# Chime_PCB_v2_511.net
KiCad netlist of a schematic drawn in EAGLE
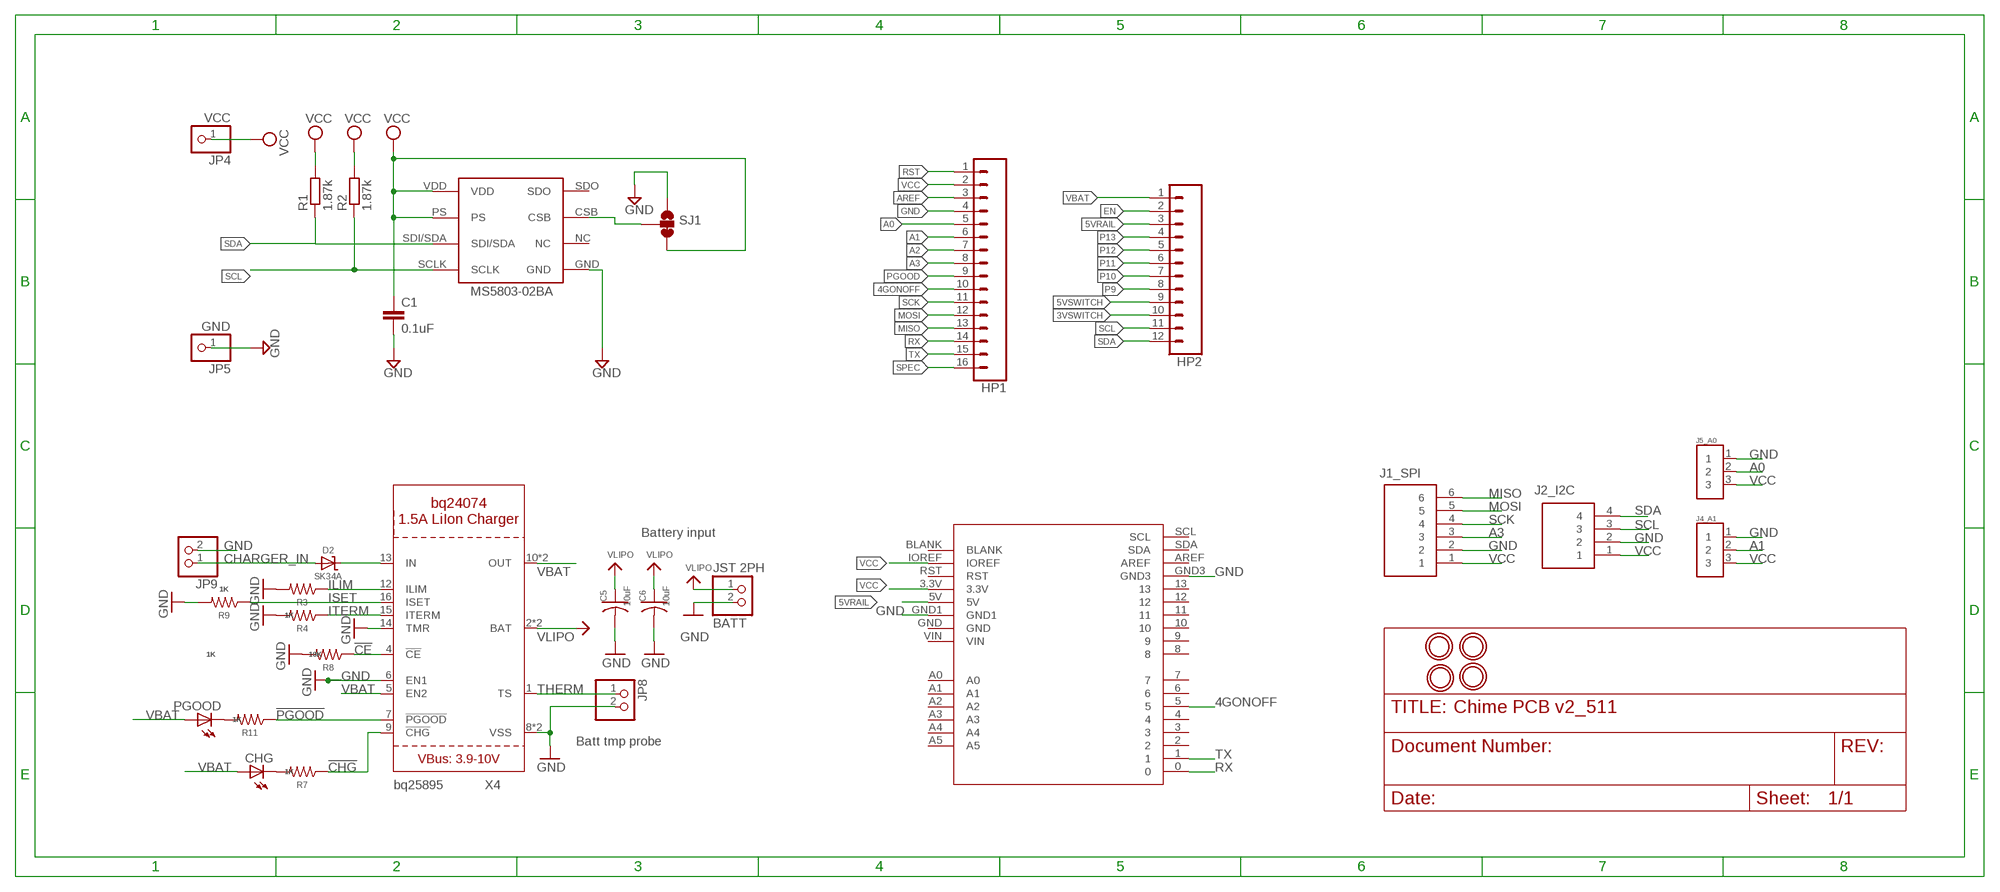
[diagram p0: schematic, sheet 1]

(export (version "E")
  (design (tool "Eeschema 10.0.6"))
  (components
    (comp (ref "BATT")
      (value "JST 2PH")
      (footprint "eagle-import:JST-PH-2-SMT-RA")
      (libsource (lib "eagle-import") (part "JST_2PIN-SMT-RA"))
    )
    (comp (ref "C1")
      (value "0.1uF")
      (footprint "eagle-import:C0805")
      (libsource (lib "eagle-import") (part "C-EUC0805"))
    )
    (comp (ref "C5")
      (value "10uF")
      (footprint "eagle-import:C0805K")
      (libsource (lib "eagle-import") (part "C-USC0805K"))
    )
    (comp (ref "C6")
      (value "10uF")
      (footprint "eagle-import:C0805K")
      (libsource (lib "eagle-import") (part "C-USC0805K"))
    )
    (comp (ref "CHG")
      (value "LEDCHIPLED_0805")
      (footprint "eagle-import:CHIPLED_0805")
      (libsource (lib "eagle-import") (part "LEDCHIPLED_0805"))
    )
    (comp (ref "D2")
      (value "SK34A")
      (footprint "eagle-import:SMADIODE")
      (libsource (lib "eagle-import") (part "DIODE-SCHOTTKYSMA"))
    )
    (comp (ref "HP1")
      (value "CONN_16")
      (footprint "eagle-import:1X16")
      (libsource (lib "eagle-import") (part "CONN_16"))
    )
    (comp (ref "HP2")
      (value "CONN_12")
      (footprint "eagle-import:1X12")
      (libsource (lib "eagle-import") (part "CONN_12"))
    )
    (comp (ref "J1_SPI")
      (value "1725698")
      (footprint "eagle-import:1725698")
      (fields (field (name "MOUSER_PART_NUMBER") "651-1725698"))
      (libsource (lib "eagle-import") (part "1725698"))
    )
    (comp (ref "J2_I2C")
      (value "1725672")
      (footprint "eagle-import:1725672")
      (fields (field (name "MOUSER_PART_NUMBER") "651-1725672"))
      (libsource (lib "eagle-import") (part "1725672"))
    )
    (comp (ref "J4_A1")
      (value "282834-3")
      (footprint "eagle-import:TE_282834-3")
      (fields (field (name "MF") "TE Connectivity"))
      (libsource (lib "eagle-import") (part "282834-3"))
    )
    (comp (ref "J5_A0")
      (value "282834-3")
      (footprint "eagle-import:TE_282834-3")
      (fields (field (name "MF") "TE Connectivity"))
      (libsource (lib "eagle-import") (part "282834-3"))
    )
    (comp (ref "JP4")
      (value "VCC")
      (footprint "eagle-import:1X01")
      (libsource (lib "eagle-import") (part "PINHD-1X1"))
    )
    (comp (ref "JP5")
      (value "GND")
      (footprint "eagle-import:1X01")
      (libsource (lib "eagle-import") (part "PINHD-1X1"))
    )
    (comp (ref "JP8")
      (value "PINHD-1X2")
      (footprint "eagle-import:1X02")
      (libsource (lib "eagle-import") (part "PINHD-1X2"))
    )
    (comp (ref "JP9")
      (value "PINHD-1X2")
      (footprint "eagle-import:1X02")
      (libsource (lib "eagle-import") (part "PINHD-1X2"))
    )
    (comp (ref "PGOOD")
      (value "PGOOD")
      (footprint "eagle-import:CHIPLED_0805")
      (libsource (lib "eagle-import") (part "LEDCHIPLED_0805"))
    )
    (comp (ref "R1")
      (value "1.87k")
      (footprint "eagle-import:R0805")
      (libsource (lib "eagle-import") (part "R-EU_R0805"))
    )
    (comp (ref "R2")
      (value "1.87k")
      (footprint "eagle-import:R0805")
      (libsource (lib "eagle-import") (part "R-EU_R0805"))
    )
    (comp (ref "R3")
      (value "1K")
      (footprint "eagle-import:M0805")
      (libsource (lib "eagle-import") (part "R-US_M0805"))
    )
    (comp (ref "R4")
      (value "1K")
      (footprint "eagle-import:M0805")
      (libsource (lib "eagle-import") (part "R-US_M0805"))
    )
    (comp (ref "R7")
      (value "1K")
      (footprint "eagle-import:M0805")
      (libsource (lib "eagle-import") (part "R-US_M0805"))
    )
    (comp (ref "R8")
      (value "10K")
      (footprint "eagle-import:M0805")
      (libsource (lib "eagle-import") (part "R-US_M0805"))
    )
    (comp (ref "R9")
      (value "1K")
      (footprint "eagle-import:M0805")
      (libsource (lib "eagle-import") (part "R-US_M0805"))
    )
    (comp (ref "R11")
      (value "1K")
      (footprint "eagle-import:M0805")
      (libsource (lib "eagle-import") (part "R-US_M0805"))
    )
    (comp (ref "SJ1")
      (value "JUMPER-SMT_3_1-NC_TRACE_SILK")
      (footprint "eagle-import:SMT-JUMPER_3_1-NC_TRACE_SILK")
      (libsource (lib "eagle-import") (part "JUMPER-SMT_3_1-NC_TRACE_SILK"))
    )
    (comp (ref "U$1")
      (value "LTE_BOARD")
      (footprint "eagle-import:LTE_BOARD_FOOTPRINT")
      (libsource (lib "eagle-import") (part "LTE_BOARD"))
    )
    (comp (ref "U$2")
      (value "MOUNTINGHOLE2.5")
      (footprint "eagle-import:MOUNTINGHOLE_2.5_PLATED")
      (libsource (lib "eagle-import") (part "MOUNTINGHOLE2.5"))
    )
    (comp (ref "U$3")
      (value "MOUNTINGHOLE2.5")
      (footprint "eagle-import:MOUNTINGHOLE_2.5_PLATED")
      (libsource (lib "eagle-import") (part "MOUNTINGHOLE2.5"))
    )
    (comp (ref "U$4")
      (value "MOUNTINGHOLE2.5")
      (footprint "eagle-import:MOUNTINGHOLE_2.5_PLATED")
      (libsource (lib "eagle-import") (part "MOUNTINGHOLE2.5"))
    )
    (comp (ref "U$5")
      (value "MOUNTINGHOLE2.5")
      (footprint "eagle-import:MOUNTINGHOLE_2.5_PLATED")
      (libsource (lib "eagle-import") (part "MOUNTINGHOLE2.5"))
    )
    (comp (ref "U1")
      (value "MS5803-02BA")
      (footprint "eagle-import:MS5803-02BA")
      (libsource (lib "eagle-import") (part "MS5803-02BA"))
    )
    (comp (ref "X4")
      (value "BQ24074")
      (footprint "eagle-import:QFN16_3MM")
      (libsource (lib "eagle-import") (part "BQ24074"))
    )
  )
  (nets
    (net (code "1") (name "/CHARGER_IN") (class "Default")
      (node (ref "D2") (pin "A") (pinfunction "A_A") (pintype "passive"))
      (node (ref "JP9") (pin "1") (pinfunction "1_1") (pintype "passive"))
    )
    (net (code "2") (name "/ILIM") (class "Default")
      (node (ref "R3") (pin "1") (pinfunction "1_1") (pintype "passive"))
      (node (ref "X4") (pin "12") (pinfunction "ILIM_12") (pintype "input"))
    )
    (net (code "3") (name "/ISET") (class "Default")
      (node (ref "R9") (pin "1") (pinfunction "1_1") (pintype "passive"))
      (node (ref "X4") (pin "16") (pinfunction "ISET_16") (pintype "input"))
    )
    (net (code "4") (name "/ITERM") (class "Default")
      (node (ref "R4") (pin "1") (pinfunction "1_1") (pintype "passive"))
      (node (ref "X4") (pin "15") (pinfunction "ITERM_15") (pintype "input"))
    )
    (net (code "5") (name "/THERM") (class "Default")
      (node (ref "JP8") (pin "1") (pinfunction "1_1") (pintype "passive"))
      (node (ref "X4") (pin "1") (pinfunction "TS_1") (pintype "input"))
    )
    (net (code "6") (name "/~{CE}") (class "Default")
      (node (ref "R8") (pin "1") (pinfunction "1_1") (pintype "passive"))
      (node (ref "X4") (pin "4") (pinfunction "~{CE}_4") (pintype "input"))
    )
    (net (code "7") (name "/~{CHG}") (class "Default")
      (node (ref "R7") (pin "1") (pinfunction "1_1") (pintype "passive"))
      (node (ref "X4") (pin "9") (pinfunction "~{CHG}_9") (pintype "output"))
    )
    (net (code "8") (name "/~{PGOOD}") (class "Default")
      (node (ref "R11") (pin "1") (pinfunction "1_1") (pintype "passive"))
      (node (ref "X4") (pin "7") (pinfunction "~{PGOOD}_7") (pintype "output"))
    )
    (net (code "9") (name "3VSWITCH") (class "Default")
      (node (ref "HP2") (pin "10") (pinfunction "10_10") (pintype "passive"))
    )
    (net (code "10") (name "4GONOFF") (class "Default")
      (node (ref "HP1") (pin "10") (pinfunction "10_10") (pintype "passive"))
      (node (ref "U$1") (pin "5") (pinfunction "5_5") (pintype "bidirectional"))
    )
    (net (code "11") (name "5VRAIL") (class "Default")
      (node (ref "HP2") (pin "3") (pinfunction "3_3") (pintype "passive"))
      (node (ref "U$1") (pin "5V") (pinfunction "5V_5V") (pintype "bidirectional"))
    )
    (net (code "12") (name "5VSWITCH") (class "Default")
      (node (ref "HP2") (pin "9") (pinfunction "9_9") (pintype "passive"))
    )
    (net (code "13") (name "A0") (class "Default")
      (node (ref "HP1") (pin "5") (pinfunction "5_5") (pintype "passive"))
      (node (ref "J5_A0") (pin "2") (pinfunction "2_2") (pintype "passive"))
    )
    (net (code "14") (name "A1") (class "Default")
      (node (ref "HP1") (pin "6") (pinfunction "6_6") (pintype "passive"))
      (node (ref "J4_A1") (pin "2") (pinfunction "2_2") (pintype "passive"))
    )
    (net (code "15") (name "A2") (class "Default")
      (node (ref "HP1") (pin "7") (pinfunction "7_7") (pintype "passive"))
    )
    (net (code "16") (name "A3") (class "Default")
      (node (ref "HP1") (pin "8") (pinfunction "8_8") (pintype "passive"))
      (node (ref "J1_SPI") (pin "3") (pinfunction "3_3") (pintype "bidirectional"))
    )
    (net (code "17") (name "AREF") (class "Default")
      (node (ref "HP1") (pin "3") (pinfunction "3_3") (pintype "passive"))
    )
    (net (code "18") (name "EN") (class "Default")
      (node (ref "HP2") (pin "2") (pinfunction "2_2") (pintype "passive"))
    )
    (net (code "19") (name "GND") (class "Default")
      (node (ref "BATT") (pin "2") (pinfunction "1_2") (pintype "passive"))
      (node (ref "C1") (pin "2") (pinfunction "2_2") (pintype "passive"))
      (node (ref "C5") (pin "2") (pinfunction "2_2") (pintype "passive"))
      (node (ref "C6") (pin "2") (pinfunction "2_2") (pintype "passive"))
      (node (ref "HP1") (pin "4") (pinfunction "4_4") (pintype "passive"))
      (node (ref "J1_SPI") (pin "2") (pinfunction "2_2") (pintype "bidirectional"))
      (node (ref "J2_I2C") (pin "2") (pinfunction "2_2") (pintype "bidirectional"))
      (node (ref "J4_A1") (pin "1") (pinfunction "1_1") (pintype "passive"))
      (node (ref "J5_A0") (pin "1") (pinfunction "1_1") (pintype "passive"))
      (node (ref "JP5") (pin "1") (pinfunction "1_1") (pintype "passive"))
      (node (ref "JP8") (pin "2") (pinfunction "2_2") (pintype "passive"))
      (node (ref "JP9") (pin "2") (pinfunction "2_2") (pintype "passive"))
      (node (ref "R3") (pin "2") (pinfunction "2_2") (pintype "passive"))
      (node (ref "R4") (pin "2") (pinfunction "2_2") (pintype "passive"))
      (node (ref "R8") (pin "2") (pinfunction "2_2") (pintype "passive"))
      (node (ref "R9") (pin "2") (pinfunction "2_2") (pintype "passive"))
      (node (ref "SJ1") (pin "1") (pinfunction "1_1") (pintype "passive"))
      (node (ref "U$1") (pin "GND1") (pinfunction "GND1_GND1") (pintype "bidirectional"))
      (node (ref "U$1") (pin "GND3") (pinfunction "GND3_GND3") (pintype "bidirectional"))
      (node (ref "U1") (pin "GND") (pinfunction "GND_GND") (pintype "bidirectional"))
      (node (ref "X4") (pin "14") (pinfunction "TMR_14") (pintype "input"))
      (node (ref "X4") (pin "6") (pinfunction "EN1_6") (pintype "input"))
      (node (ref "X4") (pin "8") (pinfunction "VSS_8") (pintype "power_in"))
      (node (ref "X4") (pin "THERMAL") (pinfunction "VSS_THERMAL") (pintype "power_in"))
    )
    (net (code "20") (name "MISO") (class "Default")
      (node (ref "HP1") (pin "13") (pinfunction "13_13") (pintype "passive"))
      (node (ref "J1_SPI") (pin "6") (pinfunction "6_6") (pintype "bidirectional"))
    )
    (net (code "21") (name "MOSI") (class "Default")
      (node (ref "HP1") (pin "12") (pinfunction "12_12") (pintype "passive"))
      (node (ref "J1_SPI") (pin "5") (pinfunction "5_5") (pintype "bidirectional"))
    )
    (net (code "22") (name "Net-(CHG-PadC)") (class "Default")
      (node (ref "CHG") (pin "C") (pinfunction "C_C") (pintype "passive"))
      (node (ref "R7") (pin "2") (pinfunction "2_2") (pintype "passive"))
    )
    (net (code "23") (name "Net-(PGOOD-PadC)") (class "Default")
      (node (ref "PGOOD") (pin "C") (pinfunction "C_C") (pintype "passive"))
      (node (ref "R11") (pin "2") (pinfunction "2_2") (pintype "passive"))
    )
    (net (code "24") (name "Net-(SJ1-Pad2)") (class "Default")
      (node (ref "SJ1") (pin "2") (pinfunction "2_2") (pintype "passive"))
      (node (ref "U1") (pin "CSB") (pinfunction "CSB_CSB") (pintype "bidirectional"))
    )
    (net (code "25") (name "Net-(X4-IN)") (class "Default")
      (node (ref "D2") (pin "C") (pinfunction "C_C") (pintype "passive"))
      (node (ref "X4") (pin "13") (pinfunction "IN_13") (pintype "power_in"))
    )
    (net (code "26") (name "P9") (class "Default")
      (node (ref "HP2") (pin "8") (pinfunction "8_8") (pintype "passive"))
    )
    (net (code "27") (name "P10") (class "Default")
      (node (ref "HP2") (pin "7") (pinfunction "7_7") (pintype "passive"))
    )
    (net (code "28") (name "P11") (class "Default")
      (node (ref "HP2") (pin "6") (pinfunction "6_6") (pintype "passive"))
    )
    (net (code "29") (name "P12") (class "Default")
      (node (ref "HP2") (pin "5") (pinfunction "5_5") (pintype "passive"))
    )
    (net (code "30") (name "P13") (class "Default")
      (node (ref "HP2") (pin "4") (pinfunction "4_4") (pintype "passive"))
    )
    (net (code "31") (name "PGOOD") (class "Default")
      (node (ref "HP1") (pin "9") (pinfunction "9_9") (pintype "passive"))
    )
    (net (code "32") (name "RST") (class "Default")
      (node (ref "HP1") (pin "1") (pinfunction "1_1") (pintype "passive"))
    )
    (net (code "33") (name "RX") (class "Default")
      (node (ref "HP1") (pin "14") (pinfunction "14_14") (pintype "passive"))
      (node (ref "U$1") (pin "0") (pinfunction "0_0") (pintype "bidirectional"))
    )
    (net (code "34") (name "SCK") (class "Default")
      (node (ref "HP1") (pin "11") (pinfunction "11_11") (pintype "passive"))
      (node (ref "J1_SPI") (pin "4") (pinfunction "4_4") (pintype "bidirectional"))
    )
    (net (code "35") (name "SCL") (class "Default")
      (node (ref "HP2") (pin "11") (pinfunction "11_11") (pintype "passive"))
      (node (ref "J2_I2C") (pin "3") (pinfunction "3_3") (pintype "bidirectional"))
      (node (ref "R2") (pin "1") (pinfunction "1_1") (pintype "passive"))
      (node (ref "U1") (pin "SCLK") (pinfunction "SCLK_SCLK") (pintype "bidirectional"))
    )
    (net (code "36") (name "SDA") (class "Default")
      (node (ref "HP2") (pin "12") (pinfunction "12_12") (pintype "passive"))
      (node (ref "J2_I2C") (pin "4") (pinfunction "4_4") (pintype "bidirectional"))
      (node (ref "R1") (pin "1") (pinfunction "1_1") (pintype "passive"))
      (node (ref "U1") (pin "SDI/SDA") (pinfunction "SDI/SDA_SDI/SDA") (pintype "bidirectional"))
    )
    (net (code "37") (name "SPEC") (class "Default")
      (node (ref "HP1") (pin "16") (pinfunction "16_16") (pintype "passive"))
    )
    (net (code "38") (name "TX") (class "Default")
      (node (ref "HP1") (pin "15") (pinfunction "15_15") (pintype "passive"))
      (node (ref "U$1") (pin "1") (pinfunction "1_1") (pintype "bidirectional"))
    )
    (net (code "39") (name "VBAT") (class "Default")
      (node (ref "CHG") (pin "A") (pinfunction "A_A") (pintype "passive"))
      (node (ref "HP2") (pin "1") (pinfunction "1_1") (pintype "passive"))
      (node (ref "PGOOD") (pin "A") (pinfunction "A_A") (pintype "passive"))
      (node (ref "X4") (pin "10") (pinfunction "OUT_10") (pintype "output"))
      (node (ref "X4") (pin "11") (pinfunction "OUT_11") (pintype "output"))
      (node (ref "X4") (pin "5") (pinfunction "EN2_5") (pintype "input"))
    )
    (net (code "40") (name "VCC") (class "Default")
      (node (ref "C1") (pin "1") (pinfunction "1_1") (pintype "passive"))
      (node (ref "HP1") (pin "2") (pinfunction "2_2") (pintype "passive"))
      (node (ref "J1_SPI") (pin "1") (pinfunction "1_1") (pintype "bidirectional"))
      (node (ref "J2_I2C") (pin "1") (pinfunction "1_1") (pintype "bidirectional"))
      (node (ref "J4_A1") (pin "3") (pinfunction "3_3") (pintype "passive"))
      (node (ref "J5_A0") (pin "3") (pinfunction "3_3") (pintype "passive"))
      (node (ref "JP4") (pin "1") (pinfunction "1_1") (pintype "passive"))
      (node (ref "R1") (pin "2") (pinfunction "2_2") (pintype "passive"))
      (node (ref "R2") (pin "2") (pinfunction "2_2") (pintype "passive"))
      (node (ref "SJ1") (pin "3") (pinfunction "3_3") (pintype "passive"))
      (node (ref "U$1") (pin "3.3V") (pinfunction "3.3V_3.3V") (pintype "bidirectional"))
      (node (ref "U$1") (pin "IOREF") (pinfunction "IOREF_IOREF") (pintype "bidirectional"))
      (node (ref "U1") (pin "PS") (pinfunction "PS_PS") (pintype "bidirectional"))
      (node (ref "U1") (pin "VDD") (pinfunction "VDD_VDD") (pintype "bidirectional"))
    )
    (net (code "41") (name "VLIPO") (class "Default")
      (node (ref "BATT") (pin "1") (pinfunction "2_1") (pintype "passive"))
      (node (ref "C5") (pin "1") (pinfunction "1_1") (pintype "passive"))
      (node (ref "C6") (pin "1") (pinfunction "1_1") (pintype "passive"))
      (node (ref "X4") (pin "2") (pinfunction "BAT_2") (pintype "input"))
      (node (ref "X4") (pin "3") (pinfunction "BAT_3") (pintype "input"))
    )
    (net (code "42") (name "unconnected-(U$1-Pad2)") (class "Default")
      (node (ref "U$1") (pin "2") (pinfunction "2_2") (pintype "bidirectional"))
    )
    (net (code "43") (name "unconnected-(U$1-Pad3)") (class "Default")
      (node (ref "U$1") (pin "3") (pinfunction "3_3") (pintype "bidirectional"))
    )
    (net (code "44") (name "unconnected-(U$1-Pad4)") (class "Default")
      (node (ref "U$1") (pin "4") (pinfunction "4_4") (pintype "bidirectional"))
    )
    (net (code "45") (name "unconnected-(U$1-Pad6)") (class "Default")
      (node (ref "U$1") (pin "6") (pinfunction "6_6") (pintype "bidirectional"))
    )
    (net (code "46") (name "unconnected-(U$1-Pad7)") (class "Default")
      (node (ref "U$1") (pin "7") (pinfunction "7_7") (pintype "bidirectional"))
    )
    (net (code "47") (name "unconnected-(U$1-Pad8)") (class "Default")
      (node (ref "U$1") (pin "8") (pinfunction "8_8") (pintype "bidirectional"))
    )
    (net (code "48") (name "unconnected-(U$1-Pad9)") (class "Default")
      (node (ref "U$1") (pin "9") (pinfunction "9_9") (pintype "bidirectional"))
    )
    (net (code "49") (name "unconnected-(U$1-Pad10)") (class "Default")
      (node (ref "U$1") (pin "10") (pinfunction "10_10") (pintype "bidirectional"))
    )
    (net (code "50") (name "unconnected-(U$1-Pad11)") (class "Default")
      (node (ref "U$1") (pin "11") (pinfunction "11_11") (pintype "bidirectional"))
    )
    (net (code "51") (name "unconnected-(U$1-Pad12)") (class "Default")
      (node (ref "U$1") (pin "12") (pinfunction "12_12") (pintype "bidirectional"))
    )
    (net (code "52") (name "unconnected-(U$1-Pad13)") (class "Default")
      (node (ref "U$1") (pin "13") (pinfunction "13_13") (pintype "bidirectional"))
    )
    (net (code "53") (name "unconnected-(U$1-PadA0)") (class "Default")
      (node (ref "U$1") (pin "A0") (pinfunction "A0_A0") (pintype "bidirectional"))
    )
    (net (code "54") (name "unconnected-(U$1-PadA1)") (class "Default")
      (node (ref "U$1") (pin "A1") (pinfunction "A1_A1") (pintype "bidirectional"))
    )
    (net (code "55") (name "unconnected-(U$1-PadA2)") (class "Default")
      (node (ref "U$1") (pin "A2") (pinfunction "A2_A2") (pintype "bidirectional"))
    )
    (net (code "56") (name "unconnected-(U$1-PadA3)") (class "Default")
      (node (ref "U$1") (pin "A3") (pinfunction "A3_A3") (pintype "bidirectional"))
    )
    (net (code "57") (name "unconnected-(U$1-PadA4)") (class "Default")
      (node (ref "U$1") (pin "A4") (pinfunction "A4_A4") (pintype "bidirectional"))
    )
    (net (code "58") (name "unconnected-(U$1-PadA5)") (class "Default")
      (node (ref "U$1") (pin "A5") (pinfunction "A5_A5") (pintype "bidirectional"))
    )
    (net (code "59") (name "unconnected-(U$1-PadAREF)") (class "Default")
      (node (ref "U$1") (pin "AREF") (pinfunction "AREF_AREF") (pintype "bidirectional"))
    )
    (net (code "60") (name "unconnected-(U$1-PadBLANK)") (class "Default")
      (node (ref "U$1") (pin "BLANK") (pinfunction "BLANK_BLANK") (pintype "bidirectional"))
    )
    (net (code "61") (name "unconnected-(U$1-PadGND)") (class "Default")
      (node (ref "U$1") (pin "GND") (pinfunction "GND_GND") (pintype "bidirectional"))
    )
    (net (code "62") (name "unconnected-(U$1-PadRST)") (class "Default")
      (node (ref "U$1") (pin "RST") (pinfunction "RST_RST") (pintype "bidirectional"))
    )
    (net (code "63") (name "unconnected-(U$1-PadSCL)") (class "Default")
      (node (ref "U$1") (pin "SCL") (pinfunction "SCL_SCL") (pintype "bidirectional"))
    )
    (net (code "64") (name "unconnected-(U$1-PadSDA)") (class "Default")
      (node (ref "U$1") (pin "SDA") (pinfunction "SDA_SDA") (pintype "bidirectional"))
    )
    (net (code "65") (name "unconnected-(U$1-PadVIN)") (class "Default")
      (node (ref "U$1") (pin "VIN") (pinfunction "VIN_VIN") (pintype "bidirectional"))
    )
    (net (code "66") (name "unconnected-(U1-PadNC)") (class "Default")
      (node (ref "U1") (pin "NC") (pinfunction "NC_NC") (pintype "bidirectional"))
    )
    (net (code "67") (name "unconnected-(U1-PadSDO)") (class "Default")
      (node (ref "U1") (pin "SDO") (pinfunction "SDO_SDO") (pintype "bidirectional"))
    )
  )
)
